# main.net
KiCad netlist of a schematic drawn in Altium Designer
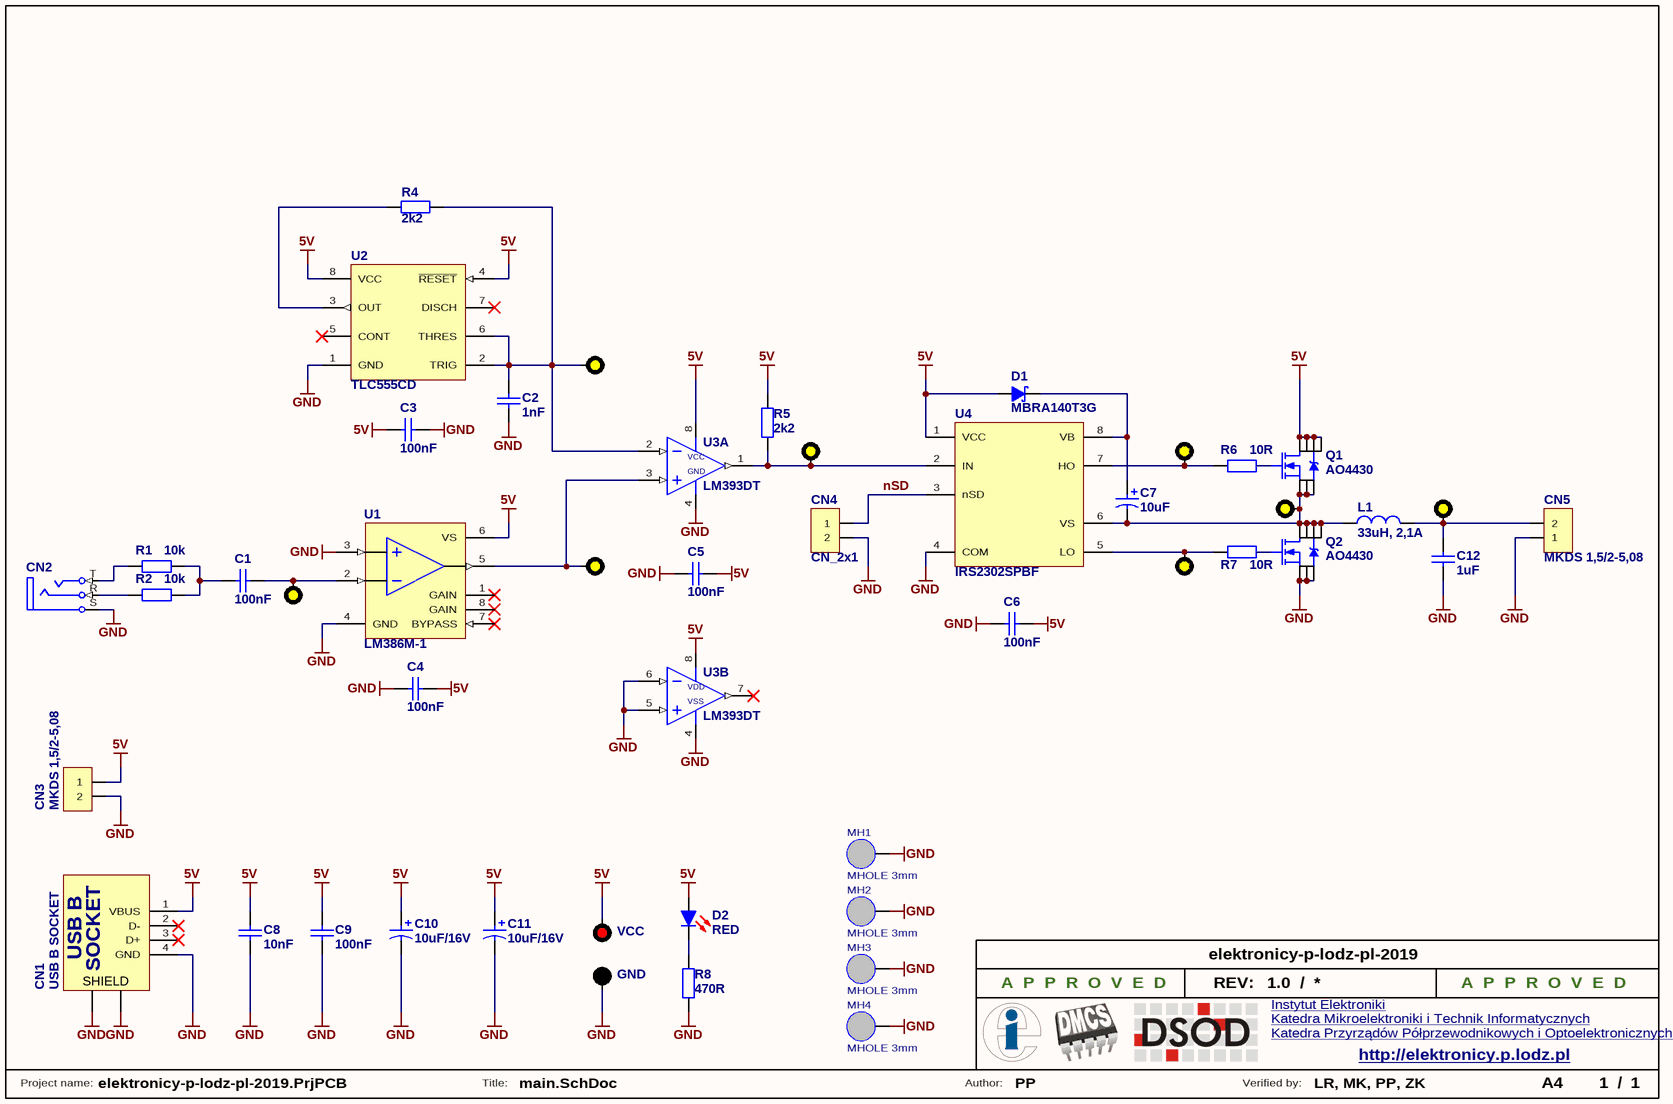
[diagram p0: main.SchDoc]

(export (version "E")
  (design (tool "Eeschema 10.0.6"))
  (components
    (comp (ref "C1")
      (value "100nF")
      (footprint "C1206")
      (description "Capacitor")
      (libsource (lib "capacitors") (part "Cap"))
    )
    (comp (ref "C2")
      (value "1nF")
      (footprint "C1206")
      (description "Capacitor")
      (libsource (lib "capacitors") (part "Cap"))
    )
    (comp (ref "C3")
      (value "100nF")
      (footprint "C1206")
      (description "Capacitor")
      (libsource (lib "capacitors") (part "Cap"))
    )
    (comp (ref "C4")
      (value "100nF")
      (footprint "C1206")
      (description "Capacitor")
      (libsource (lib "capacitors") (part "Cap"))
    )
    (comp (ref "C5")
      (value "100nF")
      (footprint "C1206")
      (description "Capacitor")
      (libsource (lib "capacitors") (part "Cap"))
    )
    (comp (ref "C6")
      (value "100nF")
      (footprint "C1206")
      (description "Capacitor")
      (libsource (lib "capacitors") (part "Cap"))
    )
    (comp (ref "C7")
      (value "10uF")
      (footprint "CE5x7-2")
      (description "Polarized Capacitor")
      (libsource (lib "capacitors") (part "Cap Pol"))
    )
    (comp (ref "C8")
      (value "10nF")
      (footprint "C1206")
      (description "Capacitor")
      (libsource (lib "capacitors") (part "Cap"))
    )
    (comp (ref "C9")
      (value "100nF")
      (footprint "C1206")
      (description "Capacitor")
      (libsource (lib "capacitors") (part "Cap"))
    )
    (comp (ref "C10")
      (value "10uF/16V")
      (footprint "CE5x7-2")
      (description "Polarized Capacitor")
      (libsource (lib "capacitors") (part "Cap Pol"))
    )
    (comp (ref "C11")
      (value "10uF/16V")
      (footprint "CE5x7-2")
      (description "Polarized Capacitor")
      (libsource (lib "capacitors") (part "Cap Pol"))
    )
    (comp (ref "C12")
      (value "1uF")
      (footprint "C1206")
      (description "Capacitor")
      (libsource (lib "capacitors") (part "Cap"))
    )
    (comp (ref "CN1")
      (value "USB B SOCKET")
      (footprint "USBB-G")
      (description "USB connector")
      (libsource (lib "usb") (part "USB B SOCKET"))
    )
    (comp (ref "CN2")
      (value "Lumberg 1503-08, Jack 3.5mm TRS")
      (footprint "LUMBERG_1503_07")
      (fields (field (name "PUBLISHER") "Altium Limited"))
      (libsource (lib "jack_trs") (part "1503-08"))
    )
    (comp (ref "CN3")
      (value "MKDS 1,5/2-5,08")
      (footprint "ARK2/3.5mm PITCH")
      (description "Phoenix Contact MKDS 1,5, PITCH 5,08mm Terminal Block")
      (libsource (lib "") (part "MKDS 1,5/2-5,08_1"))
    )
    (comp (ref "CN4") (value "CN_2x1") (footprint "GP_2x1") (libsource (lib "goldpin_male") (part "CN_2x1")))
    (comp (ref "CN5")
      (value "MKDS 1,5/2-5,08")
      (footprint "ARK2/3.5mm PITCH")
      (description "Phoenix Contact MKDS 1,5, PITCH 5,08mm Terminal Block")
      (libsource (lib "terminal_blocks") (part "MKDS 1,5/2-5,08"))
    )
    (comp (ref "D1")
      (value "MBRA140T3G")
      (footprint "SMA")
      (description "Schottky barrier rectifier: 40V, 1A")
      (libsource (lib "diodes_schottky") (part "MBRA140T3G"))
    )
    (comp (ref "D2")
      (value "RED")
      (footprint "LED1206R")
      (description "RED LED")
      (libsource (lib "leds") (part "LED_RED"))
    )
    (comp (ref "GND")
      (value "Test Point BLACK")
      (footprint "CHINA_BLACK")
      (libsource (lib "test_points") (part "Test Point BLACK"))
    )
    (comp (ref "L1")
      (value "33uH, 2,1A")
      (footprint "UNIVERSAL: DE12xx, DE07xx, DLxx,")
      (description "DE1205-33")
      (libsource (lib "inductors") (part "DE1205-33_UNIVERSAL"))
    )
    (comp (ref "MH1")
      (value "MHOLE 3mm")
      (footprint "3mm screw drill III")
      (description "3mm Mounting Hole")
      (libsource (lib "mechanical_other") (part "MHOLE_3MM"))
    )
    (comp (ref "MH2")
      (value "MHOLE 3mm")
      (footprint "3mm screw drill III")
      (description "3mm Mounting Hole")
      (libsource (lib "mechanical_other") (part "MHOLE_3MM"))
    )
    (comp (ref "MH3")
      (value "MHOLE 3mm")
      (footprint "3mm screw drill III")
      (description "3mm Mounting Hole")
      (libsource (lib "mechanical_other") (part "MHOLE_3MM"))
    )
    (comp (ref "MH4")
      (value "MHOLE 3mm")
      (footprint "3mm screw drill III")
      (description "3mm Mounting Hole")
      (libsource (lib "mechanical_other") (part "MHOLE_3MM"))
    )
    (comp (ref "Q1")
      (value "AO4430")
      (footprint "SO8")
      (description "30V N-Channel MOSFET")
      (fields (field (name "PUBLISHER") "Altium Limited"))
      (libsource (lib "transistors_mos") (part "AO4430"))
    )
    (comp (ref "Q2")
      (value "AO4430")
      (footprint "SO8")
      (description "30V N-Channel MOSFET")
      (fields (field (name "PUBLISHER") "Altium Limited"))
      (libsource (lib "transistors_mos") (part "AO4430"))
    )
    (comp (ref "R1")
      (value "10k")
      (footprint "R1206")
      (description "Resistor")
      (libsource (lib "") (part "Res_3"))
    )
    (comp (ref "R2")
      (value "10k")
      (footprint "R1206")
      (description "Resistor")
      (libsource (lib "") (part "Res_3"))
    )
    (comp (ref "R4")
      (value "2k2")
      (footprint "R1206")
      (description "Resistor")
      (libsource (lib "") (part "Res_2"))
    )
    (comp (ref "R5")
      (value "2k2")
      (footprint "R1206")
      (description "Resistor")
      (libsource (lib "") (part "Res_2"))
    )
    (comp (ref "R6")
      (value "10R")
      (footprint "R1206")
      (description "Resistor")
      (libsource (lib "resistors") (part "Res"))
    )
    (comp (ref "R7")
      (value "10R")
      (footprint "R1206")
      (description "Resistor")
      (libsource (lib "resistors") (part "Res"))
    )
    (comp (ref "R8")
      (value "470R")
      (footprint "R1206")
      (description "Resistor")
      (libsource (lib "") (part "Res_1"))
    )
    (comp (ref "TP0")
      (value "Test Point YELLOW")
      (footprint "CHINA_YELLOW")
      (libsource (lib "test_points") (part "Test Point YELLOW"))
    )
    (comp (ref "TP1")
      (value "Test Point YELLOW")
      (footprint "CHINA_YELLOW")
      (libsource (lib "test_points") (part "Test Point YELLOW"))
    )
    (comp (ref "TP2")
      (value "Test Point YELLOW")
      (footprint "CHINA_YELLOW")
      (libsource (lib "test_points") (part "Test Point YELLOW"))
    )
    (comp (ref "TP3")
      (value "Test Point YELLOW")
      (footprint "CHINA_YELLOW")
      (libsource (lib "test_points") (part "Test Point YELLOW"))
    )
    (comp (ref "TP4")
      (value "Test Point YELLOW")
      (footprint "CHINA_YELLOW")
      (libsource (lib "test_points") (part "Test Point YELLOW"))
    )
    (comp (ref "TP5")
      (value "Test Point YELLOW")
      (footprint "CHINA_YELLOW")
      (libsource (lib "test_points") (part "Test Point YELLOW"))
    )
    (comp (ref "TP6")
      (value "Test Point YELLOW")
      (footprint "CHINA_YELLOW")
      (libsource (lib "test_points") (part "Test Point YELLOW"))
    )
    (comp (ref "TP7")
      (value "Test Point YELLOW")
      (footprint "CHINA_YELLOW")
      (libsource (lib "test_points") (part "Test Point YELLOW"))
    )
    (comp (ref "U1")
      (value "LM386M-1")
      (footprint "SO8")
      (description "Dual Operational Amplifier")
      (libsource (lib "opamps") (part "LM386M-1"))
    )
    (comp (ref "U2")
      (value "TLC555CD")
      (footprint "SO8")
      (description "Precision LinCMOS™ Timer")
      (libsource (lib "ics_other") (part "TLC555CD"))
    )
    (comp (ref "U3")
      (value "LM393DT")
      (footprint "SO8")
      (description "Low power dual voltage comparators")
      (libsource (lib "comparators") (part "LM393DT"))
    )
    (comp (ref "U4")
      (value "IRS2302SPBF")
      (footprint "SO8")
      (description "Half bridge driver")
      (libsource (lib "transistor_drivers") (part "IRS2302SPBF"))
    )
    (comp (ref "VCC")
      (value "Test Point RED")
      (footprint "CHINA_RED")
      (libsource (lib "test_points") (part "Test Point RED"))
    )
  )
  (nets
    (net (code "1") (name "/nSD") (class "Default")
      (node (ref "CN4") (pin "1") (pinfunction "1_1") (pintype "passive"))
      (node (ref "U4") (pin "3") (pinfunction "nSD_3") (pintype "power_in"))
    )
    (net (code "2") (name "5V") (class "Default")
      (node (ref "C10") (pin "1") (pinfunction "1_1") (pintype "passive"))
      (node (ref "C11") (pin "1") (pinfunction "1_1") (pintype "passive"))
      (node (ref "C3") (pin "1") (pinfunction "1_1") (pintype "passive"))
      (node (ref "C4") (pin "1") (pinfunction "1_1") (pintype "passive"))
      (node (ref "C5") (pin "1") (pinfunction "1_1") (pintype "passive"))
      (node (ref "C6") (pin "1") (pinfunction "1_1") (pintype "passive"))
      (node (ref "C8") (pin "2") (pinfunction "2_2") (pintype "passive"))
      (node (ref "C9") (pin "2") (pinfunction "2_2") (pintype "passive"))
      (node (ref "CN1") (pin "1") (pinfunction "VBUS_1") (pintype "passive"))
      (node (ref "CN3") (pin "1") (pinfunction "1_1") (pintype "passive"))
      (node (ref "D1") (pin "1") (pinfunction "A_1") (pintype "passive"))
      (node (ref "D2") (pin "1") (pinfunction "A_1") (pintype "passive"))
      (node (ref "Q1") (pin "5") (pinfunction "5_5") (pintype "passive"))
      (node (ref "Q1") (pin "6") (pinfunction "6_6") (pintype "passive"))
      (node (ref "Q1") (pin "7") (pinfunction "7_7") (pintype "passive"))
      (node (ref "Q1") (pin "8") (pinfunction "8_8") (pintype "passive"))
      (node (ref "R5") (pin "1") (pinfunction "1_1") (pintype "passive"))
      (node (ref "U1") (pin "6") (pinfunction "VS_6") (pintype "power_in"))
      (node (ref "U2") (pin "4") (pinfunction "~{RESET}_4") (pintype "input"))
      (node (ref "U2") (pin "8") (pinfunction "VCC_8") (pintype "passive"))
      (node (ref "U3") (pin "8") (pinfunction "V+_8") (pintype "power_in"))
      (node (ref "U4") (pin "1") (pinfunction "VCC_1") (pintype "power_in"))
      (node (ref "VCC") (pin "0") (pinfunction "0_0") (pintype "passive"))
    )
    (net (code "3") (name "GND") (class "Default")
      (node (ref "C10") (pin "2") (pinfunction "2_2") (pintype "passive"))
      (node (ref "C11") (pin "2") (pinfunction "2_2") (pintype "passive"))
      (node (ref "C12") (pin "1") (pinfunction "1_1") (pintype "passive"))
      (node (ref "C2") (pin "1") (pinfunction "1_1") (pintype "passive"))
      (node (ref "C3") (pin "2") (pinfunction "2_2") (pintype "passive"))
      (node (ref "C4") (pin "2") (pinfunction "2_2") (pintype "passive"))
      (node (ref "C5") (pin "2") (pinfunction "2_2") (pintype "passive"))
      (node (ref "C6") (pin "2") (pinfunction "2_2") (pintype "passive"))
      (node (ref "C8") (pin "1") (pinfunction "1_1") (pintype "passive"))
      (node (ref "C9") (pin "1") (pinfunction "1_1") (pintype "passive"))
      (node (ref "CN1") (pin "4") (pinfunction "GND_4") (pintype "passive"))
      (node (ref "CN1") (pin "5") (pinfunction "SHIELD_5") (pintype "passive"))
      (node (ref "CN1") (pin "6") (pinfunction "SHIELD_6") (pintype "passive"))
      (node (ref "CN2") (pin "S") (pinfunction "S_S") (pintype "power_in"))
      (node (ref "CN3") (pin "2") (pinfunction "2_2") (pintype "passive"))
      (node (ref "CN4") (pin "2") (pinfunction "2_2") (pintype "passive"))
      (node (ref "CN5") (pin "1") (pinfunction "1_1") (pintype "passive"))
      (node (ref "GND") (pin "0") (pinfunction "0_0") (pintype "passive"))
      (node (ref "MH1") (pin "1") (pinfunction "GND_1") (pintype "passive"))
      (node (ref "MH2") (pin "1") (pinfunction "GND_1") (pintype "passive"))
      (node (ref "MH3") (pin "1") (pinfunction "GND_1") (pintype "passive"))
      (node (ref "MH4") (pin "1") (pinfunction "GND_1") (pintype "passive"))
      (node (ref "Q2") (pin "1") (pinfunction "1_1") (pintype "passive"))
      (node (ref "Q2") (pin "2") (pinfunction "2_2") (pintype "passive"))
      (node (ref "Q2") (pin "3") (pinfunction "3_3") (pintype "passive"))
      (node (ref "R8") (pin "1") (pinfunction "1_1") (pintype "passive"))
      (node (ref "U1") (pin "3") (pinfunction "IN+_3") (pintype "input"))
      (node (ref "U1") (pin "4") (pinfunction "GND_4") (pintype "power_in"))
      (node (ref "U2") (pin "1") (pinfunction "GND_1") (pintype "passive"))
      (node (ref "U3") (pin "4") (pinfunction "GND_4") (pintype "power_in"))
      (node (ref "U3") (pin "5") (pinfunction "IN+_5") (pintype "input"))
      (node (ref "U3") (pin "6") (pinfunction "IN-_6") (pintype "input"))
      (node (ref "U4") (pin "4") (pinfunction "COM_4") (pintype "power_in"))
    )
    (net (code "4") (name "Net-(C1-Pad1)") (class "Default")
      (node (ref "C1") (pin "1") (pinfunction "1_1") (pintype "passive"))
      (node (ref "R1") (pin "2") (pinfunction "2_2") (pintype "passive"))
      (node (ref "R2") (pin "2") (pinfunction "2_2") (pintype "passive"))
    )
    (net (code "5") (name "Net-(C12-Pad2)") (class "Default")
      (node (ref "C12") (pin "2") (pinfunction "2_2") (pintype "passive"))
      (node (ref "CN5") (pin "2") (pinfunction "2_2") (pintype "passive"))
      (node (ref "L1") (pin "2") (pinfunction "2_2") (pintype "passive"))
      (node (ref "TP7") (pin "0") (pinfunction "0_0") (pintype "passive"))
    )
    (net (code "6") (name "Net-(CN2-PadR)") (class "Default")
      (node (ref "CN2") (pin "R") (pinfunction "R_R") (pintype "input"))
      (node (ref "R2") (pin "1") (pinfunction "1_1") (pintype "passive"))
    )
    (net (code "7") (name "Net-(CN2-PadT)") (class "Default")
      (node (ref "CN2") (pin "T") (pinfunction "T_T") (pintype "input"))
      (node (ref "R1") (pin "1") (pinfunction "1_1") (pintype "passive"))
    )
    (net (code "8") (name "Net-(D1-K)") (class "Default")
      (node (ref "C7") (pin "1") (pinfunction "1_1") (pintype "passive"))
      (node (ref "D1") (pin "2") (pinfunction "K_2") (pintype "passive"))
      (node (ref "U4") (pin "8") (pinfunction "VB_8") (pintype "power_in"))
    )
    (net (code "9") (name "Net-(D2-K)") (class "Default")
      (node (ref "D2") (pin "2") (pinfunction "K_2") (pintype "passive"))
      (node (ref "R8") (pin "2") (pinfunction "2_2") (pintype "passive"))
    )
    (net (code "10") (name "Net-(Q1-Pad4)") (class "Default")
      (node (ref "Q1") (pin "4") (pinfunction "4_4") (pintype "passive"))
      (node (ref "R6") (pin "1") (pinfunction "1_1") (pintype "passive"))
    )
    (net (code "11") (name "Net-(Q2-Pad4)") (class "Default")
      (node (ref "Q2") (pin "4") (pinfunction "4_4") (pintype "passive"))
      (node (ref "R7") (pin "1") (pinfunction "1_1") (pintype "passive"))
    )
    (net (code "12") (name "Net-(U1-IN-)") (class "Default")
      (node (ref "C1") (pin "2") (pinfunction "2_2") (pintype "passive"))
      (node (ref "TP0") (pin "0") (pinfunction "0_0") (pintype "passive"))
      (node (ref "U1") (pin "2") (pinfunction "IN-_2") (pintype "input"))
    )
    (net (code "13") (name "Net-(U1-OUT)") (class "Default")
      (node (ref "TP1") (pin "0") (pinfunction "0_0") (pintype "passive"))
      (node (ref "U1") (pin "5") (pinfunction "OUT_5") (pintype "output"))
      (node (ref "U3") (pin "3") (pinfunction "IN+_3") (pintype "input"))
    )
    (net (code "14") (name "Net-(U2-OUT)") (class "Default")
      (node (ref "R4") (pin "2") (pinfunction "2_2") (pintype "passive"))
      (node (ref "U2") (pin "3") (pinfunction "OUT_3") (pintype "output"))
    )
    (net (code "15") (name "Net-(U2-THRES)") (class "Default")
      (node (ref "C2") (pin "2") (pinfunction "2_2") (pintype "passive"))
      (node (ref "R4") (pin "1") (pinfunction "1_1") (pintype "passive"))
      (node (ref "TP2") (pin "0") (pinfunction "0_0") (pintype "passive"))
      (node (ref "U2") (pin "2") (pinfunction "TRIG_2") (pintype "passive"))
      (node (ref "U2") (pin "6") (pinfunction "THRES_6") (pintype "passive"))
      (node (ref "U3") (pin "2") (pinfunction "IN-_2") (pintype "input"))
    )
    (net (code "16") (name "Net-(U3A-OUT)") (class "Default")
      (node (ref "R5") (pin "2") (pinfunction "2_2") (pintype "passive"))
      (node (ref "TP3") (pin "0") (pinfunction "0_0") (pintype "passive"))
      (node (ref "U3") (pin "1") (pinfunction "OUT_1") (pintype "output"))
      (node (ref "U4") (pin "2") (pinfunction "IN_2") (pintype "power_in"))
    )
    (net (code "17") (name "Net-(U4-HO)") (class "Default")
      (node (ref "R6") (pin "2") (pinfunction "2_2") (pintype "passive"))
      (node (ref "TP5") (pin "0") (pinfunction "0_0") (pintype "passive"))
      (node (ref "U4") (pin "7") (pinfunction "HO_7") (pintype "power_in"))
    )
    (net (code "18") (name "Net-(U4-LO)") (class "Default")
      (node (ref "R7") (pin "2") (pinfunction "2_2") (pintype "passive"))
      (node (ref "TP4") (pin "0") (pinfunction "0_0") (pintype "passive"))
      (node (ref "U4") (pin "5") (pinfunction "LO_5") (pintype "power_in"))
    )
    (net (code "19") (name "Net-(U4-VS)") (class "Default")
      (node (ref "C7") (pin "2") (pinfunction "2_2") (pintype "passive"))
      (node (ref "L1") (pin "1") (pinfunction "1_1") (pintype "passive"))
      (node (ref "Q1") (pin "1") (pinfunction "1_1") (pintype "passive"))
      (node (ref "Q1") (pin "2") (pinfunction "2_2") (pintype "passive"))
      (node (ref "Q1") (pin "3") (pinfunction "3_3") (pintype "passive"))
      (node (ref "Q2") (pin "5") (pinfunction "5_5") (pintype "passive"))
      (node (ref "Q2") (pin "6") (pinfunction "6_6") (pintype "passive"))
      (node (ref "Q2") (pin "7") (pinfunction "7_7") (pintype "passive"))
      (node (ref "Q2") (pin "8") (pinfunction "8_8") (pintype "passive"))
      (node (ref "TP6") (pin "0") (pinfunction "0_0") (pintype "passive"))
      (node (ref "U4") (pin "6") (pinfunction "VS_6") (pintype "power_in"))
    )
    (net (code "20") (name "unconnected-(CN1-D+-Pad3)") (class "Default")
      (node (ref "CN1") (pin "3") (pinfunction "D+_3") (pintype "passive+no_connect"))
    )
    (net (code "21") (name "unconnected-(CN1-D--Pad2)") (class "Default")
      (node (ref "CN1") (pin "2") (pinfunction "D-_2") (pintype "passive+no_connect"))
    )
    (net (code "22") (name "unconnected-(U1-BYPASS-Pad7)") (class "Default")
      (node (ref "U1") (pin "7") (pinfunction "BYPASS_7") (pintype "input+no_connect"))
    )
    (net (code "23") (name "unconnected-(U1-GAIN-Pad1)") (class "Default")
      (node (ref "U1") (pin "1") (pinfunction "GAIN_1") (pintype "power_in+no_connect"))
    )
    (net (code "24") (name "unconnected-(U1-GAIN-Pad8)") (class "Default")
      (node (ref "U1") (pin "8") (pinfunction "GAIN_8") (pintype "passive+no_connect"))
    )
    (net (code "25") (name "unconnected-(U2-CONT-Pad5)") (class "Default")
      (node (ref "U2") (pin "5") (pinfunction "CONT_5") (pintype "passive+no_connect"))
    )
    (net (code "26") (name "unconnected-(U2-DISCH-Pad7)") (class "Default")
      (node (ref "U2") (pin "7") (pinfunction "DISCH_7") (pintype "open_collector+no_connect"))
    )
    (net (code "27") (name "unconnected-(U3B-OUT-Pad7)") (class "Default")
      (node (ref "U3") (pin "7") (pinfunction "OUT_7") (pintype "output+no_connect"))
    )
  )
)
